# LEDFB.net
KiCad netlist of a schematic drawn in EAGLE
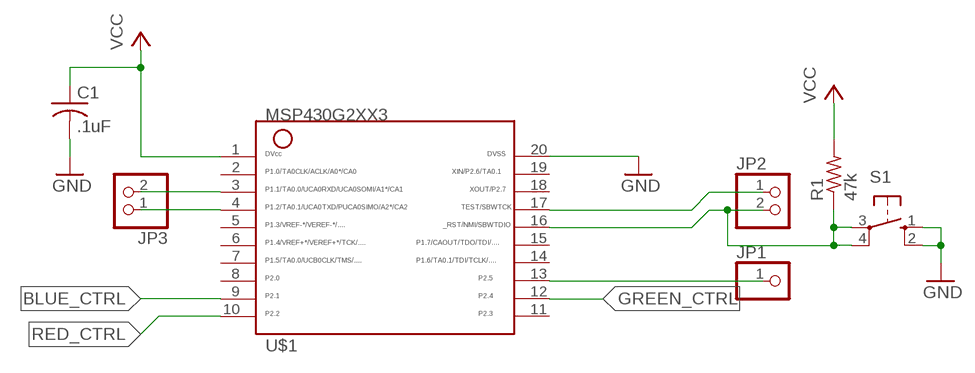
[diagram p0: schematic, sheet 1]

(export (version "E")
  (design (tool "Eeschema 10.0.6"))
  (components
    (comp (ref "C1")
      (value ".1uF")
      (footprint "eagle-import:C0805")
      (libsource (lib "eagle-import") (part "C-USC0805"))
    )
    (comp (ref "JP1")
      (value "PINHD-1X1")
      (footprint "eagle-import:1X01")
      (libsource (lib "eagle-import") (part "PINHD-1X1"))
    )
    (comp (ref "JP2")
      (value "PINHD-1X2")
      (footprint "eagle-import:1X02")
      (libsource (lib "eagle-import") (part "PINHD-1X2"))
    )
    (comp (ref "JP3")
      (value "PINHD-1X2")
      (footprint "eagle-import:1X02")
      (libsource (lib "eagle-import") (part "PINHD-1X2"))
    )
    (comp (ref "R1")
      (value "47k")
      (footprint "eagle-import:R0805")
      (libsource (lib "eagle-import") (part "R-US_R0805"))
    )
    (comp (ref "S1")
      (value "10-XX")
      (footprint "eagle-import:B3F-10XX")
      (fields (field (name "MPN") "B3F-1000"))
      (libsource (lib "eagle-import") (part "10-XX"))
    )
    (comp (ref "U$1")
      (value "G2XX3---PW20")
      (footprint "eagle-import:PW20")
      (libsource (lib "eagle-import") (part "G2XX3---PW20"))
    )
  )
  (nets
    (net (code "1") (name "BLUE_CTRL") (class "Default")
      (node (ref "U$1") (pin "9") (pinfunction "9_9") (pintype "bidirectional"))
    )
    (net (code "2") (name "GND") (class "Default")
      (node (ref "C1") (pin "2") (pinfunction "2_2") (pintype "passive"))
      (node (ref "S1") (pin "1") (pinfunction "S_1") (pintype "passive"))
      (node (ref "S1") (pin "2") (pinfunction "S1_2") (pintype "passive"))
      (node (ref "U$1") (pin "20") (pinfunction "20_20") (pintype "bidirectional"))
    )
    (net (code "3") (name "GREEN_CTRL") (class "Default")
      (node (ref "U$1") (pin "12") (pinfunction "12_12") (pintype "bidirectional"))
    )
    (net (code "4") (name "Net-(JP1-Pad1)") (class "Default")
      (node (ref "JP1") (pin "1") (pinfunction "1_1") (pintype "passive"))
      (node (ref "U$1") (pin "13") (pinfunction "13_13") (pintype "bidirectional"))
    )
    (net (code "5") (name "Net-(JP2-Pad1)") (class "Default")
      (node (ref "JP2") (pin "1") (pinfunction "1_1") (pintype "passive"))
      (node (ref "U$1") (pin "17") (pinfunction "17_17") (pintype "bidirectional"))
    )
    (net (code "6") (name "Net-(JP3-Pad1)") (class "Default")
      (node (ref "JP3") (pin "1") (pinfunction "1_1") (pintype "passive"))
      (node (ref "U$1") (pin "4") (pinfunction "4_4") (pintype "bidirectional"))
    )
    (net (code "7") (name "Net-(JP3-Pad2)") (class "Default")
      (node (ref "JP3") (pin "2") (pinfunction "2_2") (pintype "passive"))
      (node (ref "U$1") (pin "3") (pinfunction "3_3") (pintype "bidirectional"))
    )
    (net (code "8") (name "Net-(S1-P)") (class "Default")
      (node (ref "JP2") (pin "2") (pinfunction "2_2") (pintype "passive"))
      (node (ref "R1") (pin "1") (pinfunction "1_1") (pintype "passive"))
      (node (ref "S1") (pin "3") (pinfunction "P_3") (pintype "passive"))
      (node (ref "S1") (pin "4") (pinfunction "P1_4") (pintype "passive"))
      (node (ref "U$1") (pin "16") (pinfunction "16_16") (pintype "bidirectional"))
    )
    (net (code "9") (name "RED_CTRL") (class "Default")
      (node (ref "U$1") (pin "10") (pinfunction "10_10") (pintype "bidirectional"))
    )
    (net (code "10") (name "VCC") (class "Default")
      (node (ref "C1") (pin "1") (pinfunction "1_1") (pintype "passive"))
      (node (ref "R1") (pin "2") (pinfunction "2_2") (pintype "passive"))
      (node (ref "U$1") (pin "1") (pinfunction "1_1") (pintype "bidirectional"))
    )
    (net (code "11") (name "unconnected-(U$1-Pad2)") (class "Default")
      (node (ref "U$1") (pin "2") (pinfunction "2_2") (pintype "bidirectional"))
    )
    (net (code "12") (name "unconnected-(U$1-Pad5)") (class "Default")
      (node (ref "U$1") (pin "5") (pinfunction "5_5") (pintype "bidirectional"))
    )
    (net (code "13") (name "unconnected-(U$1-Pad6)") (class "Default")
      (node (ref "U$1") (pin "6") (pinfunction "6_6") (pintype "bidirectional"))
    )
    (net (code "14") (name "unconnected-(U$1-Pad7)") (class "Default")
      (node (ref "U$1") (pin "7") (pinfunction "7_7") (pintype "bidirectional"))
    )
    (net (code "15") (name "unconnected-(U$1-Pad8)") (class "Default")
      (node (ref "U$1") (pin "8") (pinfunction "8_8") (pintype "bidirectional"))
    )
    (net (code "16") (name "unconnected-(U$1-Pad11)") (class "Default")
      (node (ref "U$1") (pin "11") (pinfunction "11_11") (pintype "bidirectional"))
    )
    (net (code "17") (name "unconnected-(U$1-Pad14)") (class "Default")
      (node (ref "U$1") (pin "14") (pinfunction "14_14") (pintype "bidirectional"))
    )
    (net (code "18") (name "unconnected-(U$1-Pad15)") (class "Default")
      (node (ref "U$1") (pin "15") (pinfunction "15_15") (pintype "bidirectional"))
    )
    (net (code "19") (name "unconnected-(U$1-Pad18)") (class "Default")
      (node (ref "U$1") (pin "18") (pinfunction "18_18") (pintype "bidirectional"))
    )
    (net (code "20") (name "unconnected-(U$1-Pad19)") (class "Default")
      (node (ref "U$1") (pin "19") (pinfunction "19_19") (pintype "bidirectional"))
    )
  )
)
